# ESP_RobtB.net
KiCad netlist of a schematic drawn in EAGLE
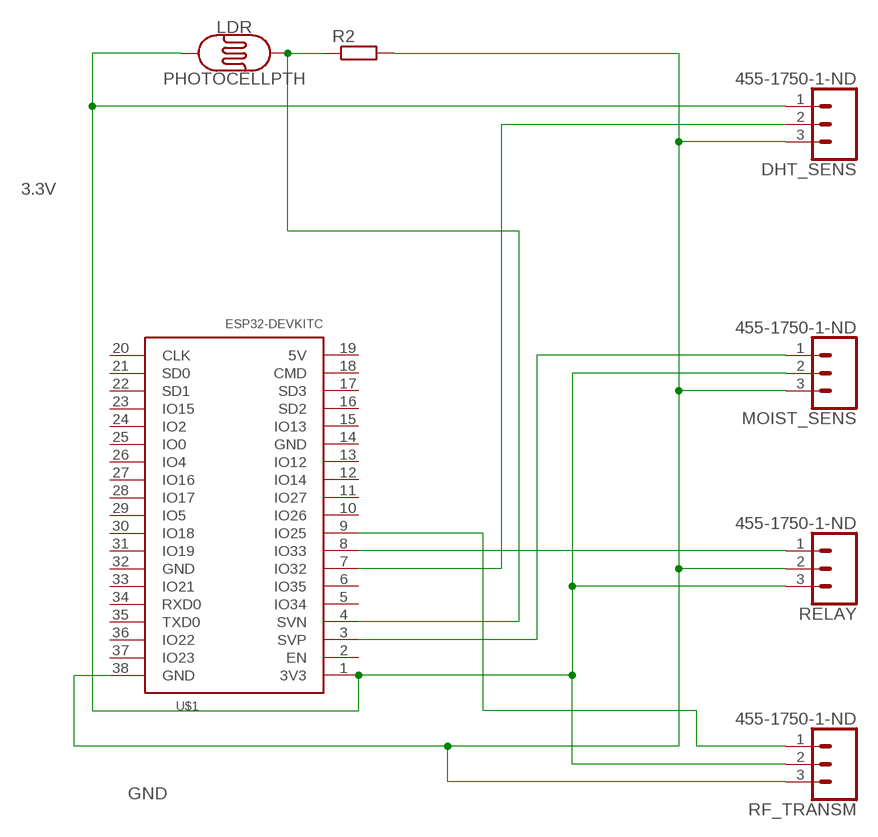
[diagram p0: schematic, sheet 1]

(export (version "E")
  (design (tool "Eeschema 10.0.6"))
  (components
    (comp (ref "DHT_SENS")
      (value "455-1750-1-ND")
      (footprint "eagle-import:1X03")
      (libsource (lib "eagle-import") (part "CONN_03"))
    )
    (comp (ref "LDR")
      (value "PHOTOCELLPTH")
      (footprint "eagle-import:PHOTOCELL")
      (libsource (lib "eagle-import") (part "PHOTOCELLPTH"))
    )
    (comp (ref "MOIST_SENS")
      (value "455-1750-1-ND")
      (footprint "eagle-import:1X03")
      (libsource (lib "eagle-import") (part "CONN_03"))
    )
    (comp (ref "R2")
      (value "R-EU_0207/10")
      (footprint "eagle-import:0207_10")
      (libsource (lib "eagle-import") (part "R-EU_0207/10"))
    )
    (comp (ref "RELAY")
      (value "455-1750-1-ND")
      (footprint "eagle-import:1X03")
      (libsource (lib "eagle-import") (part "CONN_03"))
    )
    (comp (ref "RF_TRANSM")
      (value "455-1750-1-ND")
      (footprint "eagle-import:1X03")
      (libsource (lib "eagle-import") (part "CONN_03"))
    )
    (comp (ref "U$1")
      (value "ESP32DEVKITC")
      (footprint "eagle-import:ESP32-DEVKITC")
      (libsource (lib "eagle-import") (part "ESP32DEVKITC"))
    )
  )
  (nets
    (net (code "1") (name "/3.3V") (class "Default")
      (node (ref "DHT_SENS") (pin "1") (pinfunction "1_1") (pintype "passive"))
      (node (ref "LDR") (pin "1") (pinfunction "P$1_1") (pintype "bidirectional"))
      (node (ref "MOIST_SENS") (pin "2") (pinfunction "2_2") (pintype "passive"))
      (node (ref "RELAY") (pin "3") (pinfunction "3_3") (pintype "passive"))
      (node (ref "RF_TRANSM") (pin "2") (pinfunction "2_2") (pintype "passive"))
      (node (ref "U$1") (pin "1") (pinfunction "3V3_1") (pintype "bidirectional"))
    )
    (net (code "2") (name "/GND") (class "Default")
      (node (ref "DHT_SENS") (pin "3") (pinfunction "3_3") (pintype "passive"))
      (node (ref "MOIST_SENS") (pin "3") (pinfunction "3_3") (pintype "passive"))
      (node (ref "R2") (pin "2") (pinfunction "2_2") (pintype "passive"))
      (node (ref "RELAY") (pin "2") (pinfunction "2_2") (pintype "passive"))
      (node (ref "RF_TRANSM") (pin "3") (pinfunction "3_3") (pintype "passive"))
      (node (ref "U$1") (pin "38") (pinfunction "GND_38") (pintype "bidirectional"))
    )
    (net (code "3") (name "Net-(LDR-P$2)") (class "Default")
      (node (ref "LDR") (pin "2") (pinfunction "P$2_2") (pintype "bidirectional"))
      (node (ref "R2") (pin "1") (pinfunction "1_1") (pintype "passive"))
      (node (ref "U$1") (pin "4") (pinfunction "SVN_4") (pintype "bidirectional"))
    )
    (net (code "4") (name "Net-(U$1-IO25)") (class "Default")
      (node (ref "RF_TRANSM") (pin "1") (pinfunction "1_1") (pintype "passive"))
      (node (ref "U$1") (pin "9") (pinfunction "IO25_9") (pintype "bidirectional"))
    )
    (net (code "5") (name "Net-(U$1-IO32)") (class "Default")
      (node (ref "DHT_SENS") (pin "2") (pinfunction "2_2") (pintype "passive"))
      (node (ref "U$1") (pin "7") (pinfunction "IO32_7") (pintype "bidirectional"))
    )
    (net (code "6") (name "Net-(U$1-IO33)") (class "Default")
      (node (ref "RELAY") (pin "1") (pinfunction "1_1") (pintype "passive"))
      (node (ref "U$1") (pin "8") (pinfunction "IO33_8") (pintype "bidirectional"))
    )
    (net (code "7") (name "Net-(U$1-SVP)") (class "Default")
      (node (ref "MOIST_SENS") (pin "1") (pinfunction "1_1") (pintype "passive"))
      (node (ref "U$1") (pin "3") (pinfunction "SVP_3") (pintype "bidirectional"))
    )
    (net (code "8") (name "unconnected-(U$1-5V-Pad19)") (class "Default")
      (node (ref "U$1") (pin "19") (pinfunction "5V_19") (pintype "bidirectional"))
    )
    (net (code "9") (name "unconnected-(U$1-CLK-Pad20)") (class "Default")
      (node (ref "U$1") (pin "20") (pinfunction "CLK_20") (pintype "bidirectional"))
    )
    (net (code "10") (name "unconnected-(U$1-CMD-Pad18)") (class "Default")
      (node (ref "U$1") (pin "18") (pinfunction "CMD_18") (pintype "bidirectional"))
    )
    (net (code "11") (name "unconnected-(U$1-EN-Pad2)") (class "Default")
      (node (ref "U$1") (pin "2") (pinfunction "EN_2") (pintype "bidirectional"))
    )
    (net (code "12") (name "unconnected-(U$1-GND-Pad14)") (class "Default")
      (node (ref "U$1") (pin "14") (pinfunction "GND_14") (pintype "bidirectional"))
    )
    (net (code "13") (name "unconnected-(U$1-GND-Pad32)") (class "Default")
      (node (ref "U$1") (pin "32") (pinfunction "GND_32") (pintype "bidirectional"))
    )
    (net (code "14") (name "unconnected-(U$1-IO0-Pad25)") (class "Default")
      (node (ref "U$1") (pin "25") (pinfunction "IO0_25") (pintype "bidirectional"))
    )
    (net (code "15") (name "unconnected-(U$1-IO2-Pad24)") (class "Default")
      (node (ref "U$1") (pin "24") (pinfunction "IO2_24") (pintype "bidirectional"))
    )
    (net (code "16") (name "unconnected-(U$1-IO4-Pad26)") (class "Default")
      (node (ref "U$1") (pin "26") (pinfunction "IO4_26") (pintype "bidirectional"))
    )
    (net (code "17") (name "unconnected-(U$1-IO5-Pad29)") (class "Default")
      (node (ref "U$1") (pin "29") (pinfunction "IO5_29") (pintype "bidirectional"))
    )
    (net (code "18") (name "unconnected-(U$1-IO12-Pad13)") (class "Default")
      (node (ref "U$1") (pin "13") (pinfunction "IO12_13") (pintype "bidirectional"))
    )
    (net (code "19") (name "unconnected-(U$1-IO13-Pad15)") (class "Default")
      (node (ref "U$1") (pin "15") (pinfunction "IO13_15") (pintype "bidirectional"))
    )
    (net (code "20") (name "unconnected-(U$1-IO14-Pad12)") (class "Default")
      (node (ref "U$1") (pin "12") (pinfunction "IO14_12") (pintype "bidirectional"))
    )
    (net (code "21") (name "unconnected-(U$1-IO15-Pad23)") (class "Default")
      (node (ref "U$1") (pin "23") (pinfunction "IO15_23") (pintype "bidirectional"))
    )
    (net (code "22") (name "unconnected-(U$1-IO16-Pad27)") (class "Default")
      (node (ref "U$1") (pin "27") (pinfunction "IO16_27") (pintype "bidirectional"))
    )
    (net (code "23") (name "unconnected-(U$1-IO17-Pad28)") (class "Default")
      (node (ref "U$1") (pin "28") (pinfunction "IO17_28") (pintype "bidirectional"))
    )
    (net (code "24") (name "unconnected-(U$1-IO18-Pad30)") (class "Default")
      (node (ref "U$1") (pin "30") (pinfunction "IO18_30") (pintype "bidirectional"))
    )
    (net (code "25") (name "unconnected-(U$1-IO19-Pad31)") (class "Default")
      (node (ref "U$1") (pin "31") (pinfunction "IO19_31") (pintype "bidirectional"))
    )
    (net (code "26") (name "unconnected-(U$1-IO21-Pad33)") (class "Default")
      (node (ref "U$1") (pin "33") (pinfunction "IO21_33") (pintype "bidirectional"))
    )
    (net (code "27") (name "unconnected-(U$1-IO22-Pad36)") (class "Default")
      (node (ref "U$1") (pin "36") (pinfunction "IO22_36") (pintype "bidirectional"))
    )
    (net (code "28") (name "unconnected-(U$1-IO23-Pad37)") (class "Default")
      (node (ref "U$1") (pin "37") (pinfunction "IO23_37") (pintype "bidirectional"))
    )
    (net (code "29") (name "unconnected-(U$1-IO26-Pad10)") (class "Default")
      (node (ref "U$1") (pin "10") (pinfunction "IO26_10") (pintype "bidirectional"))
    )
    (net (code "30") (name "unconnected-(U$1-IO27-Pad11)") (class "Default")
      (node (ref "U$1") (pin "11") (pinfunction "IO27_11") (pintype "bidirectional"))
    )
    (net (code "31") (name "unconnected-(U$1-IO34-Pad5)") (class "Default")
      (node (ref "U$1") (pin "5") (pinfunction "IO34_5") (pintype "bidirectional"))
    )
    (net (code "32") (name "unconnected-(U$1-IO35-Pad6)") (class "Default")
      (node (ref "U$1") (pin "6") (pinfunction "IO35_6") (pintype "bidirectional"))
    )
    (net (code "33") (name "unconnected-(U$1-RXD0-Pad34)") (class "Default")
      (node (ref "U$1") (pin "34") (pinfunction "RXD0_34") (pintype "bidirectional"))
    )
    (net (code "34") (name "unconnected-(U$1-SD0-Pad21)") (class "Default")
      (node (ref "U$1") (pin "21") (pinfunction "SD0_21") (pintype "bidirectional"))
    )
    (net (code "35") (name "unconnected-(U$1-SD1-Pad22)") (class "Default")
      (node (ref "U$1") (pin "22") (pinfunction "SD1_22") (pintype "bidirectional"))
    )
    (net (code "36") (name "unconnected-(U$1-SD2-Pad16)") (class "Default")
      (node (ref "U$1") (pin "16") (pinfunction "SD2_16") (pintype "bidirectional"))
    )
    (net (code "37") (name "unconnected-(U$1-SD3-Pad17)") (class "Default")
      (node (ref "U$1") (pin "17") (pinfunction "SD3_17") (pintype "bidirectional"))
    )
    (net (code "38") (name "unconnected-(U$1-TXD0-Pad35)") (class "Default")
      (node (ref "U$1") (pin "35") (pinfunction "TXD0_35") (pintype "bidirectional"))
    )
  )
)
